# F103H.net
KiCad netlist of a schematic drawn in Altium Designer
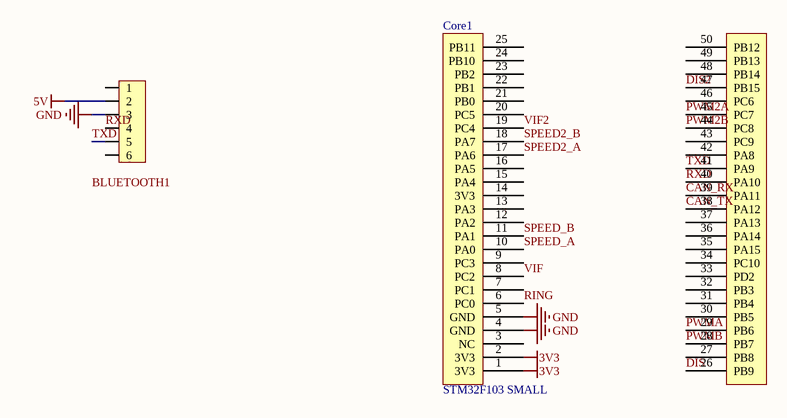
[diagram p0: F103H.SchDoc]

(export (version "E")
  (design (tool "Eeschema 10.0.6"))
  (components
    (comp (ref "BLUETOOTH1")
      (value "HDR1x6_2.54")
      (footprint "HDR1X6_2.54_180")
      (description "Header")
      (libsource (lib "Integrated_Library") (part "HDR1x6_2.54"))
    )
    (comp (ref "Core1")
      (value "STM32F103 SMALL")
      (footprint "STM32F103Small")
      (libsource (lib "K60-mainboard-v3.1") (part "STM32F103 SMALL"))
    )
  )
  (nets
    (net (code "1") (name "/CAN_RX") (class "Default")
      (node (ref "Core1") (pin "39") (pinfunction "PA11_39") (pintype "passive"))
    )
    (net (code "2") (name "/CAN_TX") (class "Default")
      (node (ref "Core1") (pin "38") (pinfunction "PA12_38") (pintype "passive"))
    )
    (net (code "3") (name "/DIS") (class "Default")
      (node (ref "Core1") (pin "26") (pinfunction "PB9_26") (pintype "passive"))
    )
    (net (code "4") (name "/DIS2") (class "Default")
      (node (ref "Core1") (pin "47") (pinfunction "PB15_47") (pintype "passive"))
    )
    (net (code "5") (name "/PWM2A") (class "Default")
      (node (ref "Core1") (pin "45") (pinfunction "PC7_45") (pintype "passive"))
    )
    (net (code "6") (name "/PWM2B") (class "Default")
      (node (ref "Core1") (pin "44") (pinfunction "PC8_44") (pintype "passive"))
    )
    (net (code "7") (name "/PWMA") (class "Default")
      (node (ref "Core1") (pin "29") (pinfunction "PB6_29") (pintype "passive"))
    )
    (net (code "8") (name "/PWMB") (class "Default")
      (node (ref "Core1") (pin "28") (pinfunction "PB7_28") (pintype "passive"))
    )
    (net (code "9") (name "/RING") (class "Default")
      (node (ref "Core1") (pin "6") (pinfunction "PC0_6") (pintype "passive"))
    )
    (net (code "10") (name "/RXD") (class "Default")
      (node (ref "BLUETOOTH1") (pin "4") (pinfunction "4_4") (pintype "passive"))
      (node (ref "Core1") (pin "40") (pinfunction "PA10_40") (pintype "passive"))
    )
    (net (code "11") (name "/SPEED2_A") (class "Default")
      (node (ref "Core1") (pin "17") (pinfunction "PA6_17") (pintype "passive"))
    )
    (net (code "12") (name "/SPEED2_B") (class "Default")
      (node (ref "Core1") (pin "18") (pinfunction "PA7_18") (pintype "passive"))
    )
    (net (code "13") (name "/SPEED_A") (class "Default")
      (node (ref "Core1") (pin "10") (pinfunction "PA0_10") (pintype "passive"))
    )
    (net (code "14") (name "/SPEED_B") (class "Default")
      (node (ref "Core1") (pin "11") (pinfunction "PA1_11") (pintype "passive"))
    )
    (net (code "15") (name "/TXD") (class "Default")
      (node (ref "BLUETOOTH1") (pin "5") (pinfunction "5_5") (pintype "passive"))
      (node (ref "Core1") (pin "41") (pinfunction "PA9_41") (pintype "passive"))
    )
    (net (code "16") (name "/VIF") (class "Default")
      (node (ref "Core1") (pin "8") (pinfunction "PC2_8") (pintype "passive"))
    )
    (net (code "17") (name "/VIF2") (class "Default")
      (node (ref "Core1") (pin "19") (pinfunction "PC4_19") (pintype "passive"))
    )
    (net (code "18") (name "3V3") (class "Default")
      (node (ref "Core1") (pin "1") (pinfunction "3V3_1") (pintype "passive"))
      (node (ref "Core1") (pin "2") (pinfunction "3V3_2") (pintype "passive"))
    )
    (net (code "19") (name "5V") (class "Default")
      (node (ref "BLUETOOTH1") (pin "2") (pinfunction "2_2") (pintype "passive"))
    )
    (net (code "20") (name "GND") (class "Default")
      (node (ref "BLUETOOTH1") (pin "3") (pinfunction "3_3") (pintype "passive"))
      (node (ref "Core1") (pin "4") (pinfunction "GND_4") (pintype "passive"))
      (node (ref "Core1") (pin "5") (pinfunction "GND_5") (pintype "passive"))
    )
    (net (code "21") (name "unconnected-(BLUETOOTH1-Pad1)") (class "Default")
      (node (ref "BLUETOOTH1") (pin "1") (pinfunction "1_1") (pintype "passive"))
    )
    (net (code "22") (name "unconnected-(BLUETOOTH1-Pad6)") (class "Default")
      (node (ref "BLUETOOTH1") (pin "6") (pinfunction "6_6") (pintype "passive"))
    )
    (net (code "23") (name "unconnected-(Core1-3V3-Pad14)") (class "Default")
      (node (ref "Core1") (pin "14") (pinfunction "3V3_14") (pintype "passive"))
    )
    (net (code "24") (name "unconnected-(Core1-NC-Pad3)") (class "Default")
      (node (ref "Core1") (pin "3") (pinfunction "NC_3") (pintype "passive"))
    )
    (net (code "25") (name "unconnected-(Core1-PA2-Pad12)") (class "Default")
      (node (ref "Core1") (pin "12") (pinfunction "PA2_12") (pintype "passive"))
    )
    (net (code "26") (name "unconnected-(Core1-PA3-Pad13)") (class "Default")
      (node (ref "Core1") (pin "13") (pinfunction "PA3_13") (pintype "passive"))
    )
    (net (code "27") (name "unconnected-(Core1-PA4-Pad15)") (class "Default")
      (node (ref "Core1") (pin "15") (pinfunction "PA4_15") (pintype "passive"))
    )
    (net (code "28") (name "unconnected-(Core1-PA5-Pad16)") (class "Default")
      (node (ref "Core1") (pin "16") (pinfunction "PA5_16") (pintype "passive"))
    )
    (net (code "29") (name "unconnected-(Core1-PA8-Pad42)") (class "Default")
      (node (ref "Core1") (pin "42") (pinfunction "PA8_42") (pintype "passive"))
    )
    (net (code "30") (name "unconnected-(Core1-PA13-Pad37)") (class "Default")
      (node (ref "Core1") (pin "37") (pinfunction "PA13_37") (pintype "passive"))
    )
    (net (code "31") (name "unconnected-(Core1-PA14-Pad36)") (class "Default")
      (node (ref "Core1") (pin "36") (pinfunction "PA14_36") (pintype "passive"))
    )
    (net (code "32") (name "unconnected-(Core1-PA15-Pad35)") (class "Default")
      (node (ref "Core1") (pin "35") (pinfunction "PA15_35") (pintype "passive"))
    )
    (net (code "33") (name "unconnected-(Core1-PB0-Pad21)") (class "Default")
      (node (ref "Core1") (pin "21") (pinfunction "PB0_21") (pintype "passive"))
    )
    (net (code "34") (name "unconnected-(Core1-PB1-Pad22)") (class "Default")
      (node (ref "Core1") (pin "22") (pinfunction "PB1_22") (pintype "passive"))
    )
    (net (code "35") (name "unconnected-(Core1-PB2-Pad23)") (class "Default")
      (node (ref "Core1") (pin "23") (pinfunction "PB2_23") (pintype "passive"))
    )
    (net (code "36") (name "unconnected-(Core1-PB3-Pad32)") (class "Default")
      (node (ref "Core1") (pin "32") (pinfunction "PB3_32") (pintype "passive"))
    )
    (net (code "37") (name "unconnected-(Core1-PB4-Pad31)") (class "Default")
      (node (ref "Core1") (pin "31") (pinfunction "PB4_31") (pintype "passive"))
    )
    (net (code "38") (name "unconnected-(Core1-PB5-Pad30)") (class "Default")
      (node (ref "Core1") (pin "30") (pinfunction "PB5_30") (pintype "passive"))
    )
    (net (code "39") (name "unconnected-(Core1-PB8-Pad27)") (class "Default")
      (node (ref "Core1") (pin "27") (pinfunction "PB8_27") (pintype "passive"))
    )
    (net (code "40") (name "unconnected-(Core1-PB10-Pad24)") (class "Default")
      (node (ref "Core1") (pin "24") (pinfunction "PB10_24") (pintype "passive"))
    )
    (net (code "41") (name "unconnected-(Core1-PB11-Pad25)") (class "Default")
      (node (ref "Core1") (pin "25") (pinfunction "PB11_25") (pintype "passive"))
    )
    (net (code "42") (name "unconnected-(Core1-PB12-Pad50)") (class "Default")
      (node (ref "Core1") (pin "50") (pinfunction "PB12_50") (pintype "passive"))
    )
    (net (code "43") (name "unconnected-(Core1-PB13-Pad49)") (class "Default")
      (node (ref "Core1") (pin "49") (pinfunction "PB13_49") (pintype "passive"))
    )
    (net (code "44") (name "unconnected-(Core1-PB14-Pad48)") (class "Default")
      (node (ref "Core1") (pin "48") (pinfunction "PB14_48") (pintype "passive"))
    )
    (net (code "45") (name "unconnected-(Core1-PC1-Pad7)") (class "Default")
      (node (ref "Core1") (pin "7") (pinfunction "PC1_7") (pintype "passive"))
    )
    (net (code "46") (name "unconnected-(Core1-PC3-Pad9)") (class "Default")
      (node (ref "Core1") (pin "9") (pinfunction "PC3_9") (pintype "passive"))
    )
    (net (code "47") (name "unconnected-(Core1-PC5-Pad20)") (class "Default")
      (node (ref "Core1") (pin "20") (pinfunction "PC5_20") (pintype "passive"))
    )
    (net (code "48") (name "unconnected-(Core1-PC6-Pad46)") (class "Default")
      (node (ref "Core1") (pin "46") (pinfunction "PC6_46") (pintype "passive"))
    )
    (net (code "49") (name "unconnected-(Core1-PC9-Pad43)") (class "Default")
      (node (ref "Core1") (pin "43") (pinfunction "PC9_43") (pintype "passive"))
    )
    (net (code "50") (name "unconnected-(Core1-PC10-Pad34)") (class "Default")
      (node (ref "Core1") (pin "34") (pinfunction "PC10_34") (pintype "passive"))
    )
    (net (code "51") (name "unconnected-(Core1-PD2-Pad33)") (class "Default")
      (node (ref "Core1") (pin "33") (pinfunction "PD2_33") (pintype "passive"))
    )
  )
)
